# Main.net
KiCad netlist of a schematic drawn in EAGLE
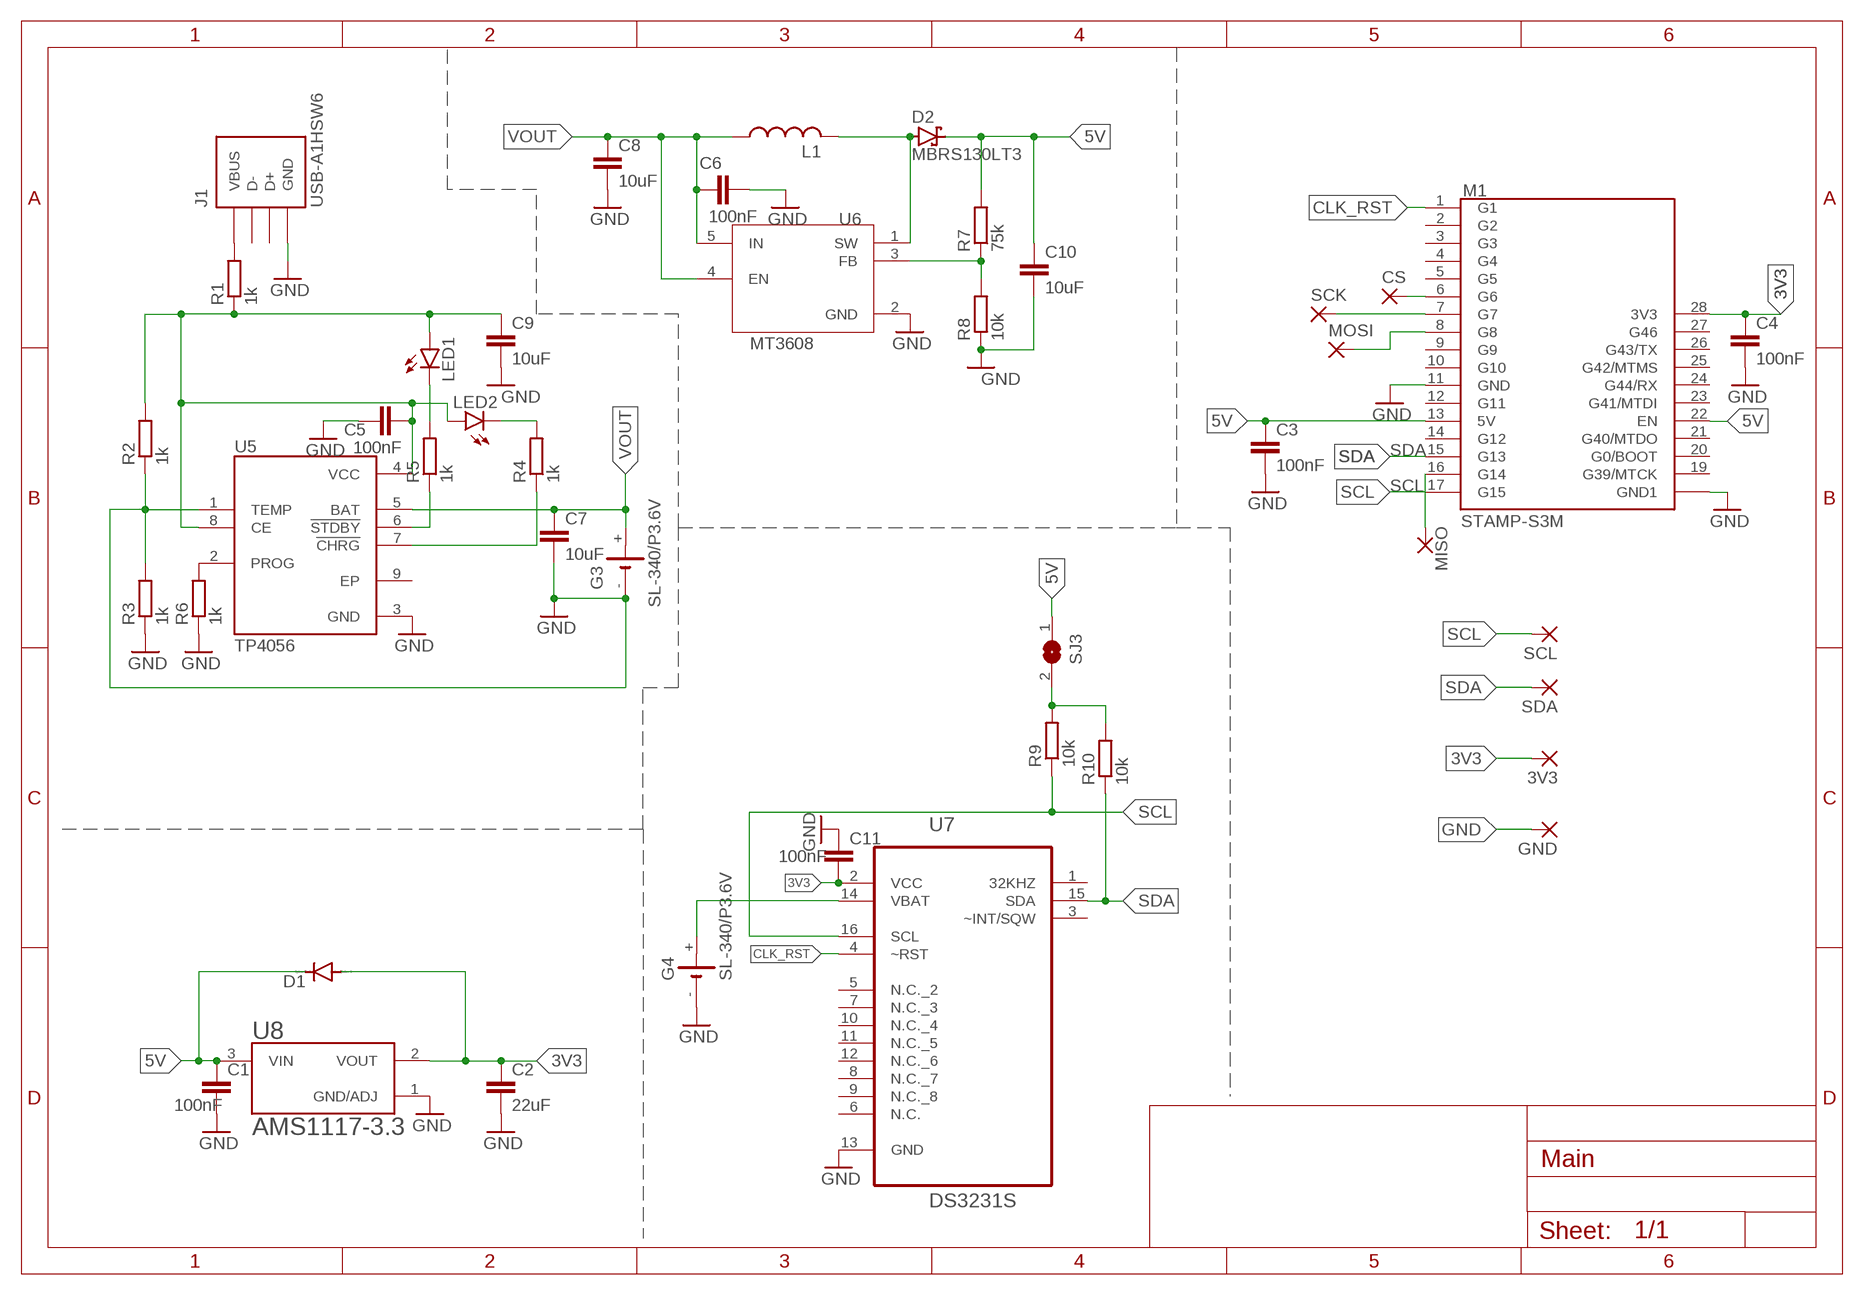
[diagram p0: schematic, sheet 1]

(export (version "E")
  (design (tool "Eeschema 10.0.6"))
  (components
    (comp (ref "3V3")
      (value "1,6/0,8")
      (footprint "eagle-import:1,6_0,8")
      (libsource (lib "eagle-import") (part "1,6/0,8"))
    )
    (comp (ref "C1")
      (value "100nF")
      (footprint "eagle-import:C0402")
      (libsource (lib "eagle-import") (part "C-EUC0402"))
    )
    (comp (ref "C2")
      (value "22uF")
      (footprint "eagle-import:C0402")
      (libsource (lib "eagle-import") (part "C-EUC0402"))
    )
    (comp (ref "C3")
      (value "100nF")
      (footprint "eagle-import:C0402")
      (libsource (lib "eagle-import") (part "C-EUC0402"))
    )
    (comp (ref "C4")
      (value "100nF")
      (footprint "eagle-import:C0402")
      (libsource (lib "eagle-import") (part "C-EUC0402"))
    )
    (comp (ref "C5")
      (value "100nF")
      (footprint "eagle-import:C0402")
      (libsource (lib "eagle-import") (part "C-EUC0402"))
    )
    (comp (ref "C6")
      (value "100nF")
      (footprint "eagle-import:C0402")
      (libsource (lib "eagle-import") (part "C-EUC0402"))
    )
    (comp (ref "C7")
      (value "10uF")
      (footprint "eagle-import:C0402")
      (libsource (lib "eagle-import") (part "C-EUC0402"))
    )
    (comp (ref "C8")
      (value "10uF")
      (footprint "eagle-import:C0402")
      (libsource (lib "eagle-import") (part "C-EUC0402"))
    )
    (comp (ref "C9")
      (value "10uF")
      (footprint "eagle-import:C0402")
      (libsource (lib "eagle-import") (part "C-EUC0402"))
    )
    (comp (ref "C10")
      (value "10uF")
      (footprint "eagle-import:C0402")
      (libsource (lib "eagle-import") (part "C-EUC0402"))
    )
    (comp (ref "C11")
      (value "100nF")
      (footprint "eagle-import:C0402")
      (libsource (lib "eagle-import") (part "C-EUC0402"))
    )
    (comp (ref "CS")
      (value "1,6/0,8")
      (footprint "eagle-import:1,6_0,8")
      (libsource (lib "eagle-import") (part "1,6/0,8"))
    )
    (comp (ref "D1")
      (value "DIODE-SMB")
      (footprint "eagle-import:SMB")
      (libsource (lib "eagle-import") (part "DIODE-SMB"))
    )
    (comp (ref "D2")
      (value "MBRS130LT3")
      (footprint "eagle-import:SMB")
      (libsource (lib "eagle-import") (part "MBRS130LT3"))
    )
    (comp (ref "G3")
      (value "SL-340/P3.6V")
      (footprint "eagle-import:SL-340_P3.6V")
      (libsource (lib "eagle-import") (part "SL-340/P3.6V"))
    )
    (comp (ref "G4")
      (value "SL-340/P3.6V")
      (footprint "eagle-import:SL-340_P3.6V")
      (libsource (lib "eagle-import") (part "SL-340/P3.6V"))
    )
    (comp (ref "GND")
      (value "1,6/0,8")
      (footprint "eagle-import:1,6_0,8")
      (libsource (lib "eagle-import") (part "1,6/0,8"))
    )
    (comp (ref "J1")
      (value "USB-A1HSW6")
      (footprint "eagle-import:OST_USB-A1HSW6")
      (fields (field (name "MF") "On Shore"))
      (libsource (lib "eagle-import") (part "USB-A1HSW6"))
    )
    (comp (ref "L1")
      (value "L-USL3225M")
      (footprint "eagle-import:L3225M")
      (libsource (lib "eagle-import") (part "L-USL3225M"))
    )
    (comp (ref "LED1")
      (value "LEDCHIPLED_0805")
      (footprint "eagle-import:CHIPLED_0805")
      (libsource (lib "eagle-import") (part "LEDCHIPLED_0805"))
    )
    (comp (ref "LED2")
      (value "LEDCHIPLED_0805")
      (footprint "eagle-import:CHIPLED_0805")
      (libsource (lib "eagle-import") (part "LEDCHIPLED_0805"))
    )
    (comp (ref "MISO")
      (value "1,6/0,8")
      (footprint "eagle-import:1,6_0,8")
      (libsource (lib "eagle-import") (part "1,6/0,8"))
    )
    (comp (ref "MOSI")
      (value "1,6/0,8")
      (footprint "eagle-import:1,6_0,8")
      (libsource (lib "eagle-import") (part "1,6/0,8"))
    )
    (comp (ref "R1")
      (value "1k")
      (footprint "eagle-import:M1206")
      (libsource (lib "eagle-import") (part "R-EU_M1206"))
    )
    (comp (ref "R2")
      (value "1k")
      (footprint "eagle-import:M1206")
      (libsource (lib "eagle-import") (part "R-EU_M1206"))
    )
    (comp (ref "R3")
      (value "1k")
      (footprint "eagle-import:M1206")
      (libsource (lib "eagle-import") (part "R-EU_M1206"))
    )
    (comp (ref "R4")
      (value "1k")
      (footprint "eagle-import:M1206")
      (libsource (lib "eagle-import") (part "R-EU_M1206"))
    )
    (comp (ref "R5")
      (value "1k")
      (footprint "eagle-import:M1206")
      (libsource (lib "eagle-import") (part "R-EU_M1206"))
    )
    (comp (ref "R6")
      (value "1k")
      (footprint "eagle-import:M1206")
      (libsource (lib "eagle-import") (part "R-EU_M1206"))
    )
    (comp (ref "R7")
      (value "75k")
      (footprint "eagle-import:M1206")
      (libsource (lib "eagle-import") (part "R-EU_M1206"))
    )
    (comp (ref "R8")
      (value "10k")
      (footprint "eagle-import:M1206")
      (libsource (lib "eagle-import") (part "R-EU_M1206"))
    )
    (comp (ref "R9")
      (value "10k")
      (footprint "eagle-import:M1206")
      (libsource (lib "eagle-import") (part "R-EU_M1206"))
    )
    (comp (ref "R10")
      (value "10k")
      (footprint "eagle-import:M1206")
      (libsource (lib "eagle-import") (part "R-EU_M1206"))
    )
    (comp (ref "SCK")
      (value "1,6/0,8")
      (footprint "eagle-import:1,6_0,8")
      (libsource (lib "eagle-import") (part "1,6/0,8"))
    )
    (comp (ref "SCL")
      (value "1,6/0,8")
      (footprint "eagle-import:1,6_0,8")
      (libsource (lib "eagle-import") (part "1,6/0,8"))
    )
    (comp (ref "SDA")
      (value "1,6/0,8")
      (footprint "eagle-import:1,6_0,8")
      (libsource (lib "eagle-import") (part "1,6/0,8"))
    )
    (comp (ref "SJ3") (value "SJ") (footprint "eagle-import:SJ") (libsource (lib "eagle-import") (part "SJ")))
    (comp (ref "U$1")
      (value "STAMP-S3M-PIN")
      (footprint "eagle-import:STAMPS3_PIN_FTP")
      (libsource (lib "eagle-import") (part "STAMP-S3M-PIN"))
    )
    (comp (ref "U5")
      (value "TP4056")
      (footprint "eagle-import:SOP127P600X175-9N")
      (fields (field (name "MF") "NanJing Top Power ASIC Corp."))
      (libsource (lib "eagle-import") (part "TP4056"))
    )
    (comp (ref "U6")
      (value "MT3608")
      (footprint "eagle-import:SOT95P280X145-6N")
      (fields (field (name "MF") "Aerosemi Technology Co., Ltd"))
      (libsource (lib "eagle-import") (part "MT3608"))
    )
    (comp (ref "U7")
      (value "DS3231S")
      (footprint "eagle-import:SOIC127P1032X265-16N")
      (fields (field (name "MF") "Analog Devices") (field (name "MP") "DS3231S#"))
      (libsource (lib "eagle-import") (part "DS3231S"))
    )
    (comp (ref "U8")
      (value "AMS1117-3.3")
      (footprint "eagle-import:SOT229P700X180-4N")
      (fields (field (name "MF") "Advanced Monolithic Systems"))
      (libsource (lib "eagle-import") (part "AMS1117-3.3"))
    )
  )
  (nets
    (net (code "1") (name "3V3") (class "Default")
      (node (ref "3V3") (pin "1") (pinfunction "P_1") (pintype "passive"))
      (node (ref "C11") (pin "2") (pinfunction "2_2") (pintype "passive"))
      (node (ref "C2") (pin "1") (pinfunction "1_1") (pintype "passive"))
      (node (ref "C4") (pin "1") (pinfunction "1_1") (pintype "passive"))
      (node (ref "D1") (pin "A") (pinfunction "A_A") (pintype "passive"))
      (node (ref "U$1") (pin "28") (pinfunction "3V3_28") (pintype "power_in"))
      (node (ref "U7") (pin "2") (pinfunction "VCC_2") (pintype "power_in"))
      (node (ref "U8") (pin "2") (pinfunction "VOUT_2") (pintype "output"))
    )
    (net (code "2") (name "5V") (class "Default")
      (node (ref "C1") (pin "1") (pinfunction "1_1") (pintype "passive"))
      (node (ref "C10") (pin "1") (pinfunction "1_1") (pintype "passive"))
      (node (ref "C3") (pin "1") (pinfunction "1_1") (pintype "passive"))
      (node (ref "D1") (pin "C") (pinfunction "C_C") (pintype "passive"))
      (node (ref "D2") (pin "C") (pinfunction "C_C") (pintype "passive"))
      (node (ref "R7") (pin "2") (pinfunction "2_2") (pintype "passive"))
      (node (ref "SJ3") (pin "1") (pinfunction "1_1") (pintype "passive"))
      (node (ref "U$1") (pin "13") (pinfunction "5V_13") (pintype "power_in"))
      (node (ref "U$1") (pin "22") (pinfunction "EN_22") (pintype "input"))
      (node (ref "U8") (pin "3") (pinfunction "VIN_3") (pintype "input"))
    )
    (net (code "3") (name "CLK_RST") (class "Default")
      (node (ref "U$1") (pin "1") (pinfunction "G1_1") (pintype "bidirectional"))
      (node (ref "U7") (pin "4") (pinfunction "~{RST}_4") (pintype "bidirectional"))
    )
    (net (code "4") (name "GND") (class "Default")
      (node (ref "C1") (pin "2") (pinfunction "2_2") (pintype "passive"))
      (node (ref "C10") (pin "2") (pinfunction "2_2") (pintype "passive"))
      (node (ref "C11") (pin "1") (pinfunction "1_1") (pintype "passive"))
      (node (ref "C2") (pin "2") (pinfunction "2_2") (pintype "passive"))
      (node (ref "C3") (pin "2") (pinfunction "2_2") (pintype "passive"))
      (node (ref "C4") (pin "2") (pinfunction "2_2") (pintype "passive"))
      (node (ref "C5") (pin "1") (pinfunction "1_1") (pintype "passive"))
      (node (ref "C6") (pin "2") (pinfunction "2_2") (pintype "passive"))
      (node (ref "C7") (pin "2") (pinfunction "2_2") (pintype "passive"))
      (node (ref "C8") (pin "2") (pinfunction "2_2") (pintype "passive"))
      (node (ref "C9") (pin "2") (pinfunction "2_2") (pintype "passive"))
      (node (ref "G3") (pin "-") (pinfunction "-_-") (pintype "passive"))
      (node (ref "G4") (pin "-") (pinfunction "-_-") (pintype "passive"))
      (node (ref "GND") (pin "1") (pinfunction "P_1") (pintype "passive"))
      (node (ref "J1") (pin "4") (pinfunction "GND_4") (pintype "power_in"))
      (node (ref "R2") (pin "1") (pinfunction "1_1") (pintype "passive"))
      (node (ref "R3") (pin "1") (pinfunction "1_1") (pintype "passive"))
      (node (ref "R3") (pin "2") (pinfunction "2_2") (pintype "passive"))
      (node (ref "R6") (pin "1") (pinfunction "1_1") (pintype "passive"))
      (node (ref "R8") (pin "1") (pinfunction "1_1") (pintype "passive"))
      (node (ref "U$1") (pin "11") (pinfunction "GND_11") (pintype "power_in"))
      (node (ref "U$1") (pin "18") (pinfunction "GND1_18") (pintype "power_in"))
      (node (ref "U5") (pin "1") (pinfunction "TEMP_1") (pintype "input"))
      (node (ref "U5") (pin "3") (pinfunction "GND_3") (pintype "power_in"))
      (node (ref "U6") (pin "2") (pinfunction "GND_2") (pintype "power_in"))
      (node (ref "U7") (pin "13") (pinfunction "GND_13") (pintype "passive"))
      (node (ref "U8") (pin "1") (pinfunction "GND/ADJ_1") (pintype "power_in"))
    )
    (net (code "5") (name "Net-(CS-P)") (class "Default")
      (node (ref "CS") (pin "1") (pinfunction "P_1") (pintype "passive"))
      (node (ref "U$1") (pin "6") (pinfunction "G6_6") (pintype "bidirectional"))
    )
    (net (code "6") (name "Net-(J1-VBUS)") (class "Default")
      (node (ref "J1") (pin "1") (pinfunction "VBUS_1") (pintype "power_in"))
      (node (ref "R1") (pin "2") (pinfunction "2_2") (pintype "passive"))
    )
    (net (code "7") (name "Net-(LED1-PadC)") (class "Default")
      (node (ref "LED1") (pin "C") (pinfunction "C_C") (pintype "passive"))
      (node (ref "R5") (pin "2") (pinfunction "2_2") (pintype "passive"))
    )
    (net (code "8") (name "Net-(LED2-PadC)") (class "Default")
      (node (ref "LED2") (pin "C") (pinfunction "C_C") (pintype "passive"))
      (node (ref "R4") (pin "2") (pinfunction "2_2") (pintype "passive"))
    )
    (net (code "9") (name "Net-(MISO-P)") (class "Default")
      (node (ref "MISO") (pin "1") (pinfunction "P_1") (pintype "passive"))
      (node (ref "U$1") (pin "16") (pinfunction "G14_16") (pintype "bidirectional"))
    )
    (net (code "10") (name "Net-(MOSI-P)") (class "Default")
      (node (ref "MOSI") (pin "1") (pinfunction "P_1") (pintype "passive"))
      (node (ref "U$1") (pin "8") (pinfunction "G8_8") (pintype "bidirectional"))
    )
    (net (code "11") (name "Net-(R10-Pad2)") (class "Default")
      (node (ref "R10") (pin "2") (pinfunction "2_2") (pintype "passive"))
      (node (ref "R9") (pin "2") (pinfunction "2_2") (pintype "passive"))
      (node (ref "SJ3") (pin "2") (pinfunction "2_2") (pintype "passive"))
    )
    (net (code "12") (name "Net-(SCK-P)") (class "Default")
      (node (ref "SCK") (pin "1") (pinfunction "P_1") (pintype "passive"))
      (node (ref "U$1") (pin "7") (pinfunction "G7_7") (pintype "bidirectional"))
    )
    (net (code "13") (name "Net-(U5-CE)") (class "Default")
      (node (ref "C5") (pin "2") (pinfunction "2_2") (pintype "passive"))
      (node (ref "C9") (pin "1") (pinfunction "1_1") (pintype "passive"))
      (node (ref "LED1") (pin "A") (pinfunction "A_A") (pintype "passive"))
      (node (ref "LED2") (pin "A") (pinfunction "A_A") (pintype "passive"))
      (node (ref "R1") (pin "1") (pinfunction "1_1") (pintype "passive"))
      (node (ref "R2") (pin "2") (pinfunction "2_2") (pintype "passive"))
      (node (ref "U5") (pin "4") (pinfunction "VCC_4") (pintype "power_in"))
      (node (ref "U5") (pin "8") (pinfunction "CE_8") (pintype "input"))
    )
    (net (code "14") (name "Net-(U5-PROG)") (class "Default")
      (node (ref "R6") (pin "2") (pinfunction "2_2") (pintype "passive"))
      (node (ref "U5") (pin "2") (pinfunction "PROG_2") (pintype "bidirectional"))
    )
    (net (code "15") (name "Net-(U5-~{CHRG})") (class "Default")
      (node (ref "R4") (pin "1") (pinfunction "1_1") (pintype "passive"))
      (node (ref "U5") (pin "7") (pinfunction "~{CHRG}_7") (pintype "output"))
    )
    (net (code "16") (name "Net-(U5-~{STDBY})") (class "Default")
      (node (ref "R5") (pin "1") (pinfunction "1_1") (pintype "passive"))
      (node (ref "U5") (pin "6") (pinfunction "~{STDBY}_6") (pintype "output"))
    )
    (net (code "17") (name "Net-(U6-FB)") (class "Default")
      (node (ref "R7") (pin "1") (pinfunction "1_1") (pintype "passive"))
      (node (ref "R8") (pin "2") (pinfunction "2_2") (pintype "passive"))
      (node (ref "U6") (pin "3") (pinfunction "FB_3") (pintype "input"))
    )
    (net (code "18") (name "Net-(U6-SW)") (class "Default")
      (node (ref "D2") (pin "A") (pinfunction "A_A") (pintype "passive"))
      (node (ref "L1") (pin "2") (pinfunction "2_2") (pintype "passive"))
      (node (ref "U6") (pin "1") (pinfunction "SW_1") (pintype "output"))
    )
    (net (code "19") (name "Net-(U7-VBAT)") (class "Default")
      (node (ref "G4") (pin "+") (pinfunction "+_+") (pintype "passive"))
      (node (ref "U7") (pin "14") (pinfunction "VBAT_14") (pintype "power_in"))
    )
    (net (code "20") (name "SCL") (class "Default")
      (node (ref "R9") (pin "1") (pinfunction "1_1") (pintype "passive"))
      (node (ref "SCL") (pin "1") (pinfunction "P_1") (pintype "passive"))
      (node (ref "U$1") (pin "17") (pinfunction "G15_17") (pintype "bidirectional"))
      (node (ref "U7") (pin "16") (pinfunction "SCL_16") (pintype "input"))
    )
    (net (code "21") (name "SDA") (class "Default")
      (node (ref "R10") (pin "1") (pinfunction "1_1") (pintype "passive"))
      (node (ref "SDA") (pin "1") (pinfunction "P_1") (pintype "passive"))
      (node (ref "U$1") (pin "15") (pinfunction "G13_15") (pintype "bidirectional"))
      (node (ref "U7") (pin "15") (pinfunction "SDA_15") (pintype "bidirectional"))
    )
    (net (code "22") (name "VOUT") (class "Default")
      (node (ref "C6") (pin "1") (pinfunction "1_1") (pintype "passive"))
      (node (ref "C7") (pin "1") (pinfunction "1_1") (pintype "passive"))
      (node (ref "C8") (pin "1") (pinfunction "1_1") (pintype "passive"))
      (node (ref "G3") (pin "+") (pinfunction "+_+") (pintype "passive"))
      (node (ref "L1") (pin "1") (pinfunction "1_1") (pintype "passive"))
      (node (ref "U5") (pin "5") (pinfunction "BAT_5") (pintype "output"))
      (node (ref "U6") (pin "4") (pinfunction "EN_4") (pintype "input"))
      (node (ref "U6") (pin "5") (pinfunction "IN_5") (pintype "input"))
    )
    (net (code "23") (name "unconnected-(J1-D+-Pad3)") (class "Default")
      (node (ref "J1") (pin "3") (pinfunction "D+_3") (pintype "bidirectional"))
    )
    (net (code "24") (name "unconnected-(J1-D--Pad2)") (class "Default")
      (node (ref "J1") (pin "2") (pinfunction "D-_2") (pintype "bidirectional"))
    )
    (net (code "25") (name "unconnected-(U$1-G0{slash}BOOT-Pad20)") (class "Default")
      (node (ref "U$1") (pin "20") (pinfunction "G0/BOOT_20") (pintype "bidirectional"))
    )
    (net (code "26") (name "unconnected-(U$1-G2-Pad2)") (class "Default")
      (node (ref "U$1") (pin "2") (pinfunction "G2_2") (pintype "bidirectional"))
    )
    (net (code "27") (name "unconnected-(U$1-G3-Pad3)") (class "Default")
      (node (ref "U$1") (pin "3") (pinfunction "G3_3") (pintype "bidirectional"))
    )
    (net (code "28") (name "unconnected-(U$1-G4-Pad4)") (class "Default")
      (node (ref "U$1") (pin "4") (pinfunction "G4_4") (pintype "bidirectional"))
    )
    (net (code "29") (name "unconnected-(U$1-G5-Pad5)") (class "Default")
      (node (ref "U$1") (pin "5") (pinfunction "G5_5") (pintype "bidirectional"))
    )
    (net (code "30") (name "unconnected-(U$1-G9-Pad9)") (class "Default")
      (node (ref "U$1") (pin "9") (pinfunction "G9_9") (pintype "bidirectional"))
    )
    (net (code "31") (name "unconnected-(U$1-G10-Pad10)") (class "Default")
      (node (ref "U$1") (pin "10") (pinfunction "G10_10") (pintype "bidirectional"))
    )
    (net (code "32") (name "unconnected-(U$1-G11-Pad12)") (class "Default")
      (node (ref "U$1") (pin "12") (pinfunction "G11_12") (pintype "bidirectional"))
    )
    (net (code "33") (name "unconnected-(U$1-G12-Pad14)") (class "Default")
      (node (ref "U$1") (pin "14") (pinfunction "G12_14") (pintype "bidirectional"))
    )
    (net (code "34") (name "unconnected-(U$1-G39{slash}MTCK-Pad19)") (class "Default")
      (node (ref "U$1") (pin "19") (pinfunction "G39/MTCK_19") (pintype "bidirectional"))
    )
    (net (code "35") (name "unconnected-(U$1-G40{slash}MTDO-Pad21)") (class "Default")
      (node (ref "U$1") (pin "21") (pinfunction "G40/MTDO_21") (pintype "bidirectional"))
    )
    (net (code "36") (name "unconnected-(U$1-G41{slash}MTDI-Pad23)") (class "Default")
      (node (ref "U$1") (pin "23") (pinfunction "G41/MTDI_23") (pintype "bidirectional"))
    )
    (net (code "37") (name "unconnected-(U$1-G42{slash}MTMS-Pad25)") (class "Default")
      (node (ref "U$1") (pin "25") (pinfunction "G42/MTMS_25") (pintype "bidirectional"))
    )
    (net (code "38") (name "unconnected-(U$1-G43{slash}TX-Pad26)") (class "Default")
      (node (ref "U$1") (pin "26") (pinfunction "G43/TX_26") (pintype "output"))
    )
    (net (code "39") (name "unconnected-(U$1-G44{slash}RX-Pad24)") (class "Default")
      (node (ref "U$1") (pin "24") (pinfunction "G44/RX_24") (pintype "input"))
    )
    (net (code "40") (name "unconnected-(U$1-G46-Pad27)") (class "Default")
      (node (ref "U$1") (pin "27") (pinfunction "G46_27") (pintype "bidirectional"))
    )
    (net (code "41") (name "unconnected-(U5-EP-Pad9)") (class "Default")
      (node (ref "U5") (pin "9") (pinfunction "EP_9") (pintype "passive"))
    )
    (net (code "42") (name "unconnected-(U7-32KHZ-Pad1)") (class "Default")
      (node (ref "U7") (pin "1") (pinfunction "32KHZ_1") (pintype "output"))
    )
    (net (code "43") (name "unconnected-(U7-N.C.-Pad6)") (class "Default")
      (node (ref "U7") (pin "6") (pinfunction "N.C._6") (pintype "no_connect"))
    )
    (net (code "44") (name "unconnected-(U7-N.C._2-Pad5)") (class "Default")
      (node (ref "U7") (pin "5") (pinfunction "N.C._2_5") (pintype "no_connect"))
    )
    (net (code "45") (name "unconnected-(U7-N.C._3-Pad7)") (class "Default")
      (node (ref "U7") (pin "7") (pinfunction "N.C._3_7") (pintype "no_connect"))
    )
    (net (code "46") (name "unconnected-(U7-N.C._4-Pad10)") (class "Default")
      (node (ref "U7") (pin "10") (pinfunction "N.C._4_10") (pintype "no_connect"))
    )
    (net (code "47") (name "unconnected-(U7-N.C._5-Pad11)") (class "Default")
      (node (ref "U7") (pin "11") (pinfunction "N.C._5_11") (pintype "no_connect"))
    )
    (net (code "48") (name "unconnected-(U7-N.C._6-Pad12)") (class "Default")
      (node (ref "U7") (pin "12") (pinfunction "N.C._6_12") (pintype "no_connect"))
    )
    (net (code "49") (name "unconnected-(U7-N.C._7-Pad8)") (class "Default")
      (node (ref "U7") (pin "8") (pinfunction "N.C._7_8") (pintype "no_connect"))
    )
    (net (code "50") (name "unconnected-(U7-N.C._8-Pad9)") (class "Default")
      (node (ref "U7") (pin "9") (pinfunction "N.C._8_9") (pintype "no_connect"))
    )
    (net (code "51") (name "unconnected-(U7-~{INT{slash}SQW}-Pad3)") (class "Default")
      (node (ref "U7") (pin "3") (pinfunction "~{INT/SQW}_3") (pintype "output"))
    )
  )
)
